# ProPrj_SPF5043_2025-07-16.net
KiCad netlist of a schematic drawn in EasyEDA Pro
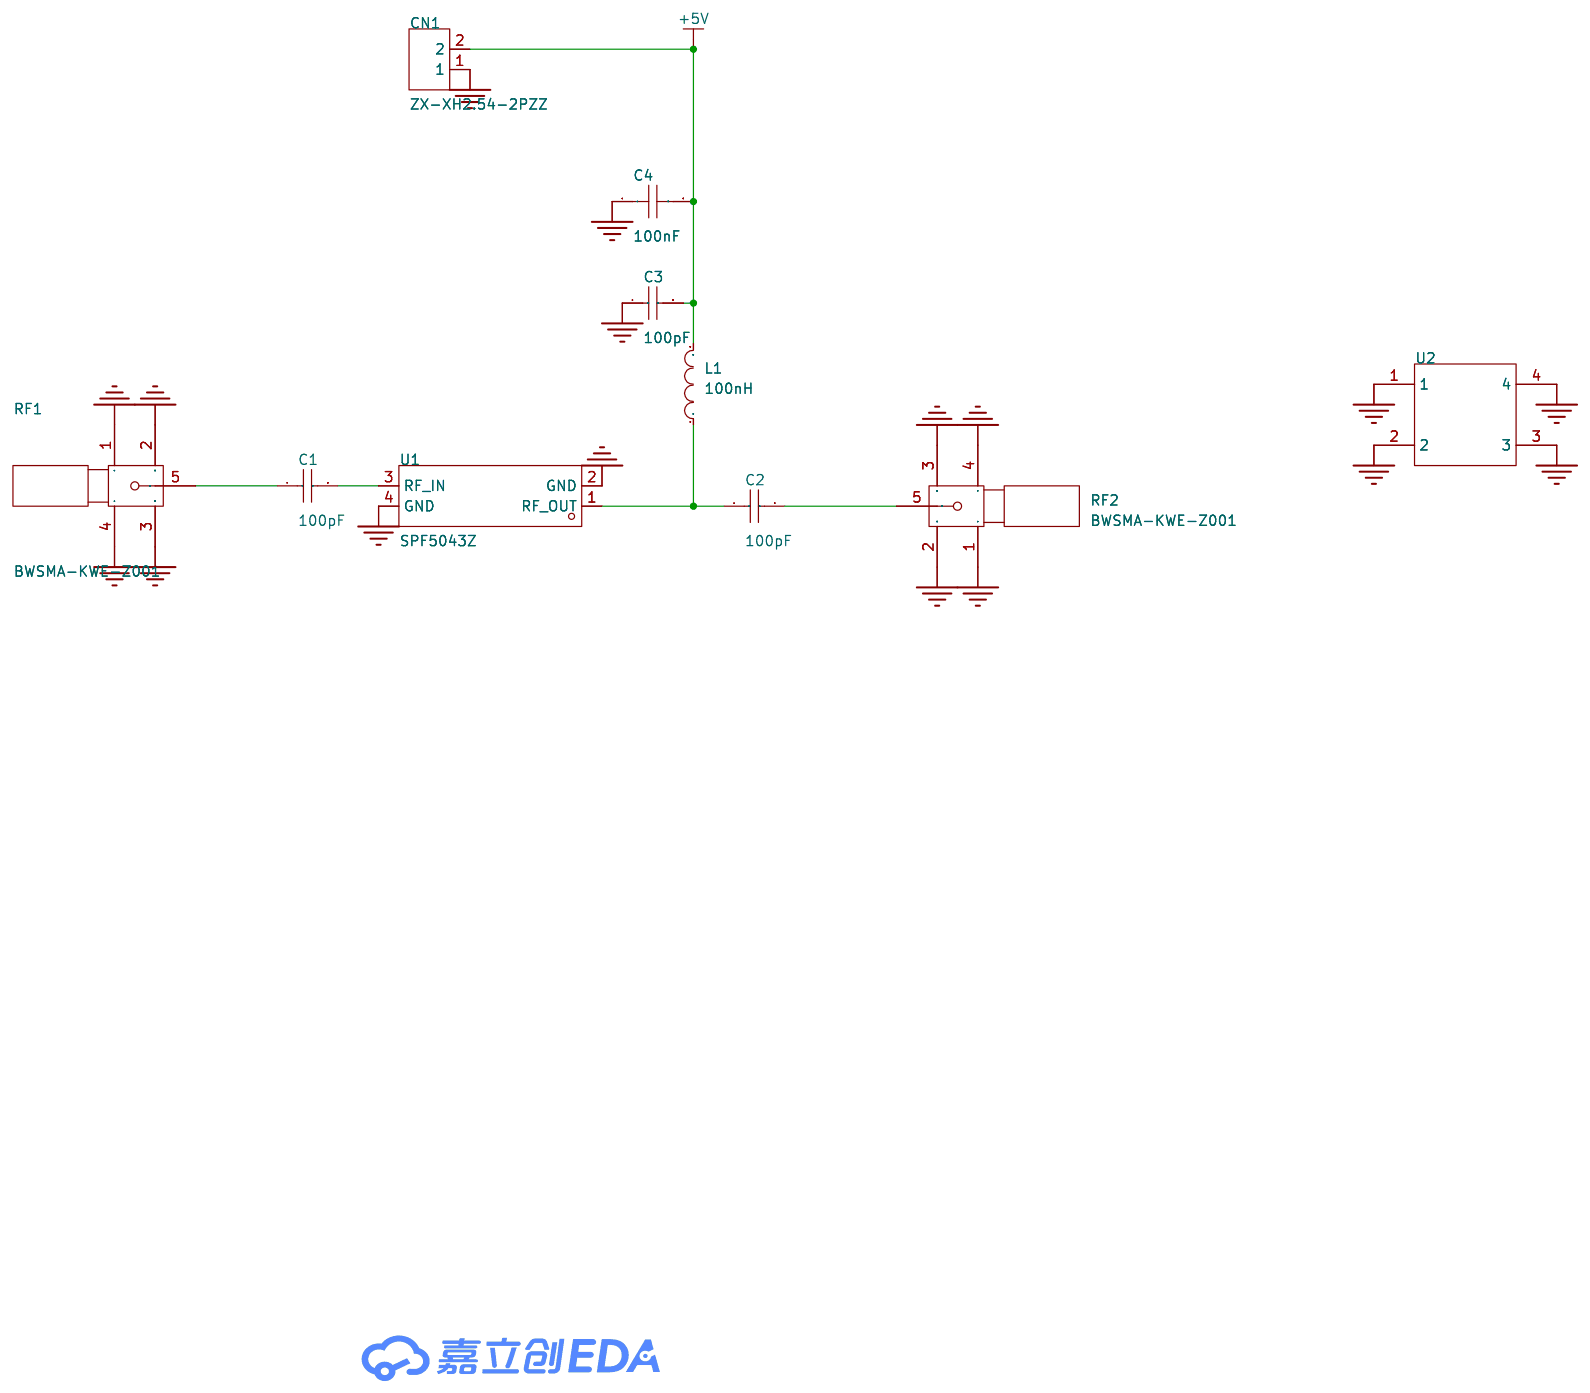
[diagram p0: schematic sheet]

(export (version "E")
  (design (tool "Eeschema 10.0.6"))
  (components
    (comp (ref "C1")
      (value "100pF")
      (footprint "easyedapro:C0603")
      (description "容值:100pF;精度:±5%;额定电压:50V;材质(温度系数):C0G;")
      (fields
        (field (name "Manufacturer Part") "CL10C101JB8NNNC")
        (field (name "Manufacturer") "SAMSUNG(三星)")
      )
      (libsource (lib "easyedapro") (part "CL10C101JB8NNNC"))
    )
    (comp (ref "C2")
      (value "100pF")
      (footprint "easyedapro:C0603")
      (description "容值:100pF;精度:±5%;额定电压:50V;材质(温度系数):C0G;")
      (fields
        (field (name "Manufacturer Part") "CL10C101JB8NNNC")
        (field (name "Manufacturer") "SAMSUNG(三星)")
      )
      (libsource (lib "easyedapro") (part "CL10C101JB8NNNC"))
    )
    (comp (ref "C3")
      (value "100pF")
      (footprint "easyedapro:C0603")
      (description "容值:100pF;精度:±5%;额定电压:50V;材质(温度系数):C0G;")
      (fields
        (field (name "Manufacturer Part") "CL10C101JB8NNNC")
        (field (name "Manufacturer") "SAMSUNG(三星)")
      )
      (libsource (lib "easyedapro") (part "CL10C101JB8NNNC"))
    )
    (comp (ref "C4")
      (value "100nF")
      (footprint "easyedapro:C0603")
      (description "容值:100nF;精度:±10%;额定电压:50V;温度系数:X7R;")
      (fields
        (field (name "Manufacturer Part") "CC0603KRX7R9BB104")
        (field (name "Manufacturer") "YAGEO(国巨)")
      )
      (libsource (lib "easyedapro") (part "CC0603KRX7R9BB104"))
    )
    (comp (ref "CN1")
      (value "ZX-XH2.54-2PZZ")
      (footprint "easyedapro:CONN-TH_2P-P2.50_HX25003-2A")
      (fields (field (name "Manufacturer") "Megastar(兆星)"))
      (libsource (lib "easyedapro") (part "ZX-XH2.54-2PZZ"))
    )
    (comp (ref "L1")
      (value "100nH")
      (footprint "easyedapro:L0603")
      (description "电感值:100nH;精度:±5%;额定电流:200mA;饱和电流(Isat):-;直流电阻(DCR):1.4Ω;")
      (fields (field (name "Manufacturer Part") "VHF160808HR10JT") (field (name "Manufacturer") "FH(风华)"))
      (libsource (lib "easyedapro") (part "VHF160808HR10JT"))
    )
    (comp (ref "RF1")
      (value "BWSMA-KWE-Z001")
      (footprint "easyedapro:SMA-TH_BWSMA-KWE-Z001")
      (fields (field (name "Manufacturer") "BAT WIRELESS(蝙蝠无线)"))
      (libsource (lib "easyedapro") (part "BWSMA-KWE-Z001"))
    )
    (comp (ref "RF2")
      (value "BWSMA-KWE-Z001")
      (footprint "easyedapro:SMA-TH_BWSMA-KWE-Z001")
      (fields (field (name "Manufacturer") "BAT WIRELESS(蝙蝠无线)"))
      (libsource (lib "easyedapro") (part "BWSMA-KWE-Z001"))
    )
    (comp (ref "U1")
      (value "SPF5043Z")
      (footprint "easyedapro:SOT343_L2.0-W1.3-P1.30-LS2.1-BL")
      (description "应用领域:手机；W-CDMA；ISM；LTE；PCS;频率:50MHz~4GHz;增益:18.2dB;噪声系数:0.8dB;")
      (fields (field (name "Manufacturer") "Qorvo"))
      (libsource (lib "easyedapro") (part "SPF5043Z"))
    )
    (comp (ref "U2")
      (value "~")
      (footprint "easyedapro:22x17x6")
      (libsource (lib "easyedapro") (part "22x17x6"))
    )
  )
  (nets
    (net (code "1") (name "+5V") (class "Default")
      (node (ref "C3") (pin "2") (pinfunction "2_2") (pintype "input"))
      (node (ref "C4") (pin "2") (pinfunction "2_2") (pintype "unspecified"))
      (node (ref "CN1") (pin "2") (pinfunction "2_2") (pintype "unspecified"))
      (node (ref "L1") (pin "2") (pinfunction "2_2") (pintype "unspecified"))
    )
    (net (code "2") (name "GND") (class "Default")
      (node (ref "C3") (pin "1") (pinfunction "1_1") (pintype "input"))
      (node (ref "C4") (pin "1") (pinfunction "1_1") (pintype "unspecified"))
      (node (ref "CN1") (pin "1") (pinfunction "1_1") (pintype "unspecified"))
      (node (ref "RF1") (pin "1") (pinfunction "1_1") (pintype "unspecified"))
      (node (ref "RF1") (pin "2") (pinfunction "2_2") (pintype "unspecified"))
      (node (ref "RF1") (pin "3") (pinfunction "3_3") (pintype "unspecified"))
      (node (ref "RF1") (pin "4") (pinfunction "4_4") (pintype "unspecified"))
      (node (ref "RF2") (pin "1") (pinfunction "1_1") (pintype "unspecified"))
      (node (ref "RF2") (pin "2") (pinfunction "2_2") (pintype "unspecified"))
      (node (ref "RF2") (pin "3") (pinfunction "3_3") (pintype "unspecified"))
      (node (ref "RF2") (pin "4") (pinfunction "4_4") (pintype "unspecified"))
      (node (ref "U1") (pin "2") (pinfunction "GND_2") (pintype "unspecified"))
      (node (ref "U1") (pin "4") (pinfunction "GND_4") (pintype "unspecified"))
      (node (ref "U2") (pin "1") (pinfunction "1_1") (pintype "input"))
      (node (ref "U2") (pin "2") (pinfunction "2_2") (pintype "input"))
      (node (ref "U2") (pin "3") (pinfunction "3_3") (pintype "input"))
      (node (ref "U2") (pin "4") (pinfunction "4_4") (pintype "input"))
    )
    (net (code "3") (name "Net-(C1-Pad1)") (class "Default")
      (node (ref "C1") (pin "1") (pinfunction "1_1") (pintype "input"))
      (node (ref "RF1") (pin "5") (pinfunction "5_5") (pintype "unspecified"))
    )
    (net (code "4") (name "Net-(C2-Pad2)") (class "Default")
      (node (ref "C2") (pin "2") (pinfunction "2_2") (pintype "input"))
      (node (ref "RF2") (pin "5") (pinfunction "5_5") (pintype "unspecified"))
    )
    (net (code "5") (name "Net-(U1-RF_IN)") (class "Default")
      (node (ref "C1") (pin "2") (pinfunction "2_2") (pintype "input"))
      (node (ref "U1") (pin "3") (pinfunction "RF_IN_3") (pintype "unspecified"))
    )
    (net (code "6") (name "Net-(U1-RF_OUT)") (class "Default")
      (node (ref "C2") (pin "1") (pinfunction "1_1") (pintype "input"))
      (node (ref "L1") (pin "1") (pinfunction "1_1") (pintype "unspecified"))
      (node (ref "U1") (pin "1") (pinfunction "RF_OUT_1") (pintype "unspecified"))
    )
  )
)
